# EuclidSeqNano_2020-09-19_20-01-49.net
KiCad netlist of a schematic drawn in EasyEDA
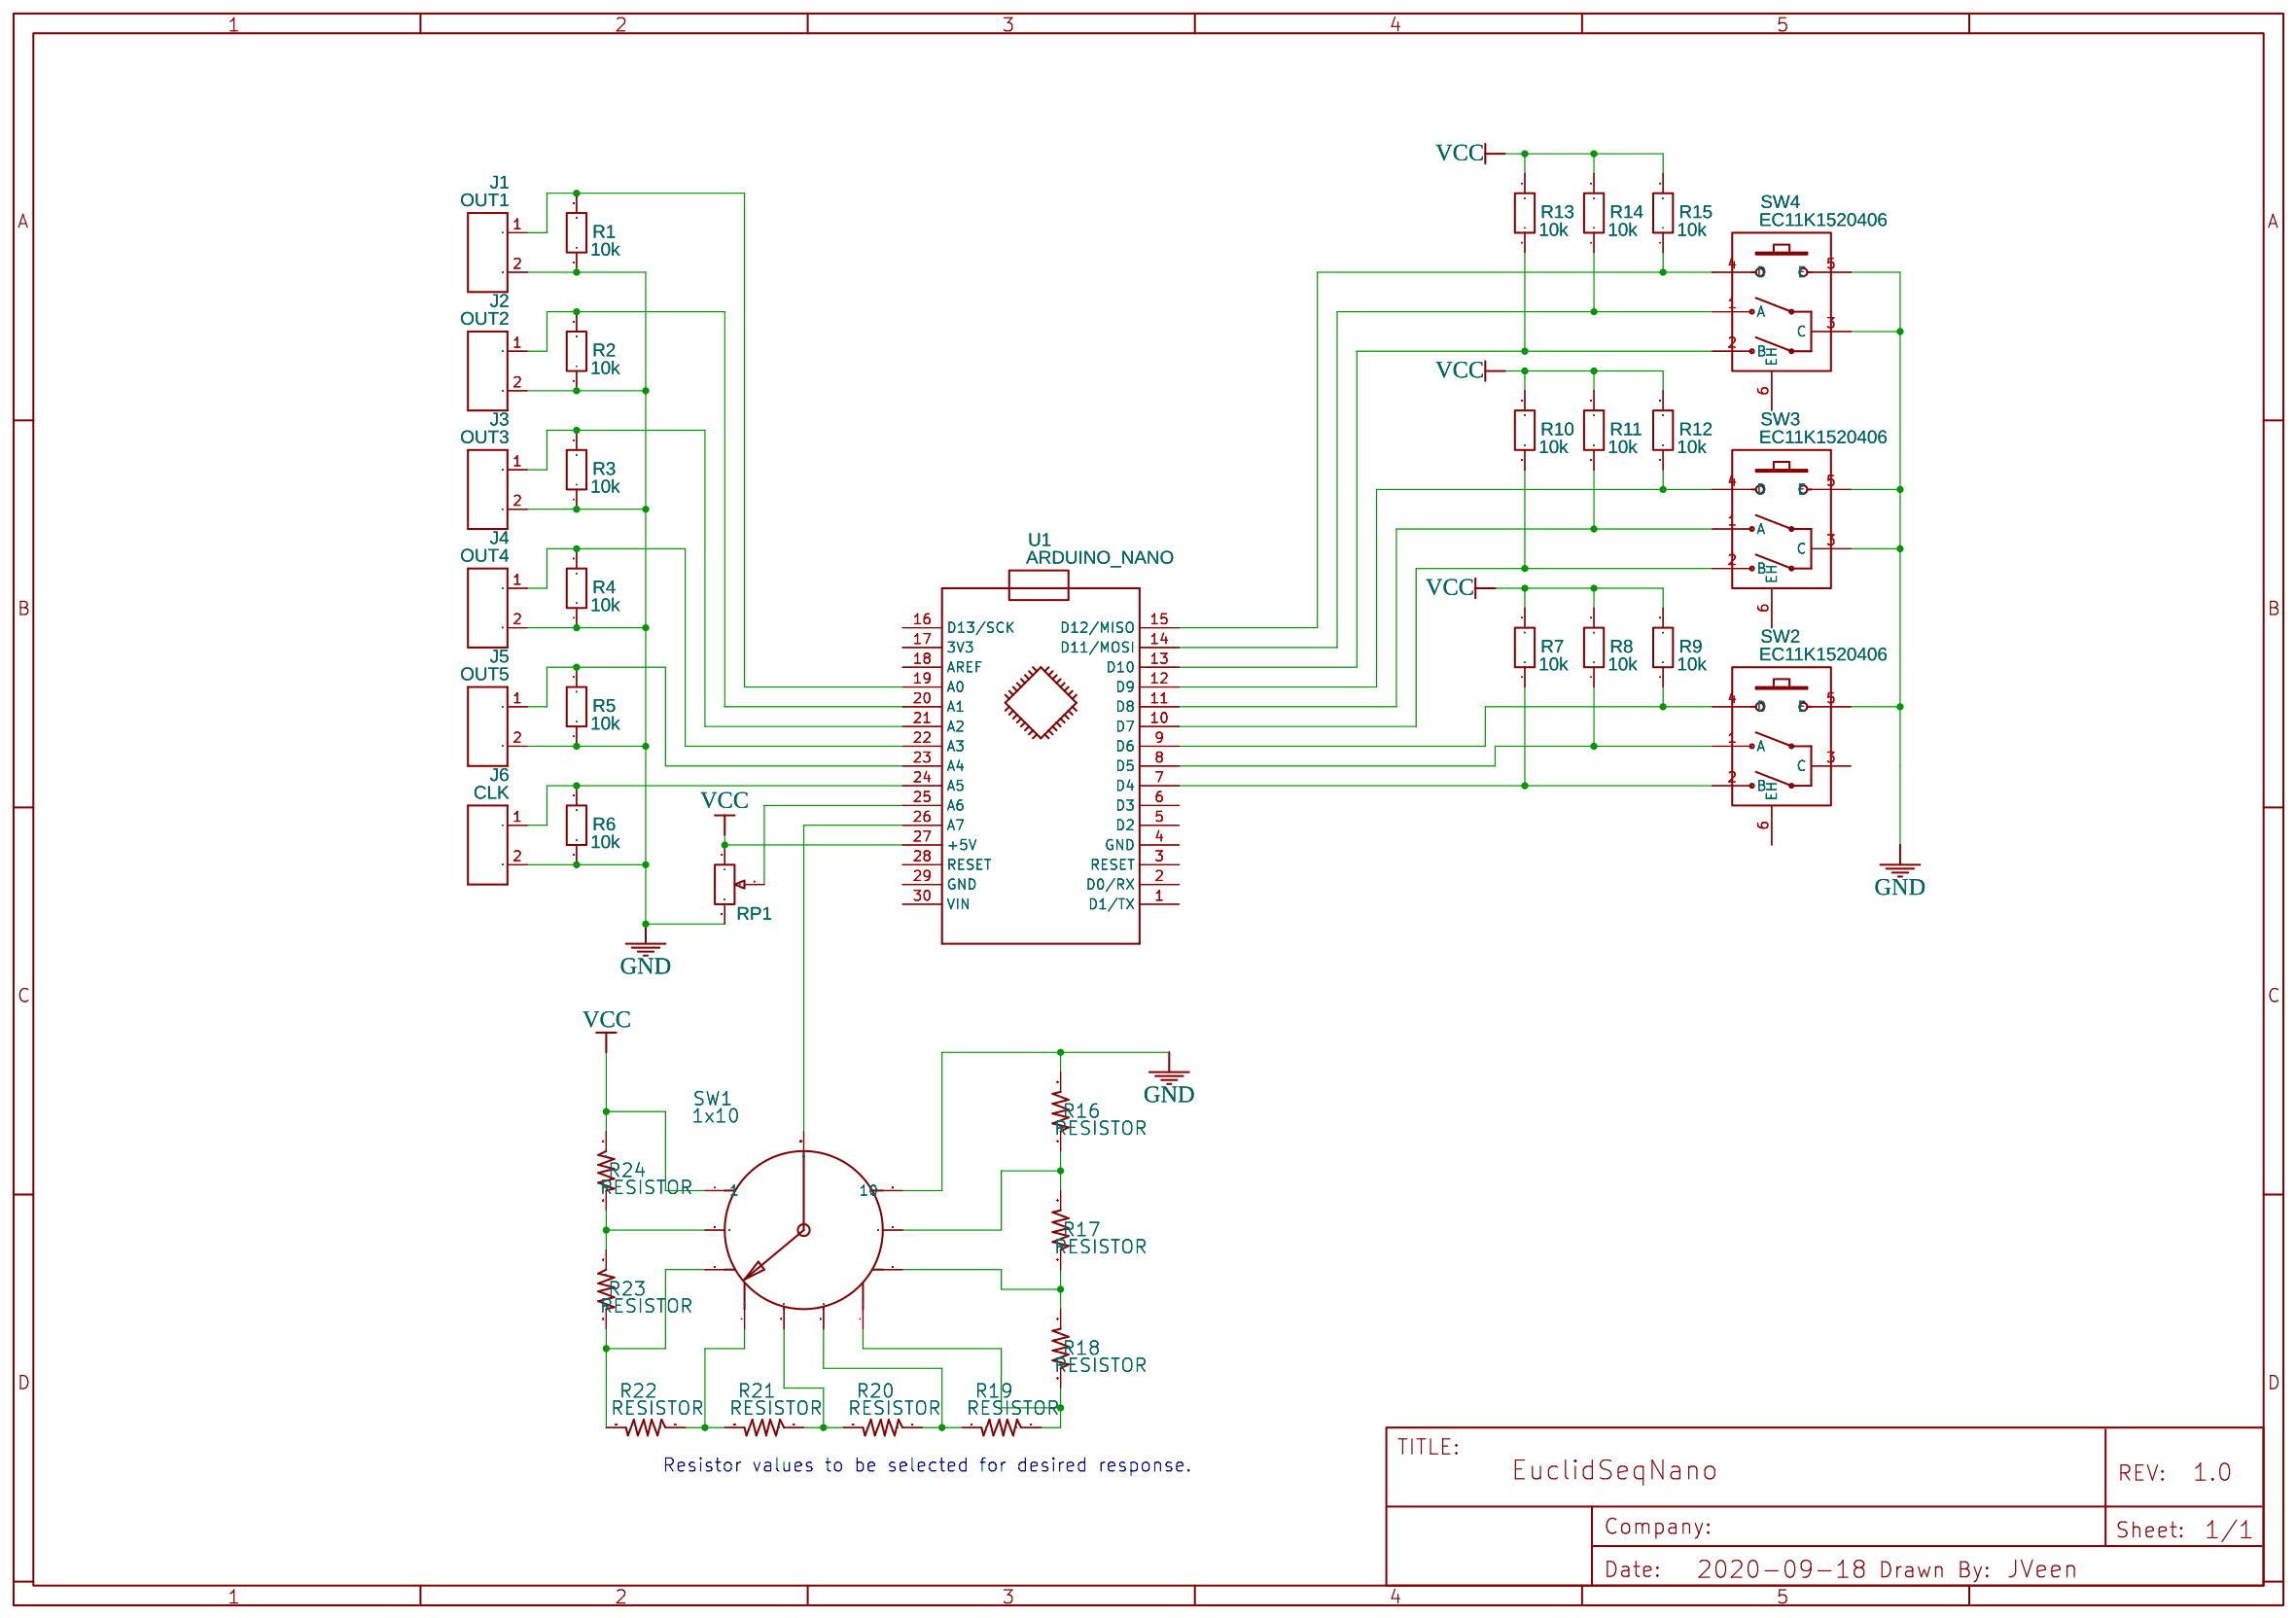
[diagram p0: schematic sheet]

(export (version "E")
  (design (tool "Eeschema 10.0.6"))
  (components
    (comp (ref "J1")
      (value "OUT1")
      (fields (field (name "BOM_Manufacturer Part") "?"))
      (libsource (lib "") (part "Unknown_245_-685"))
    )
    (comp (ref "J2")
      (value "OUT2")
      (fields (field (name "BOM_Manufacturer Part") "?"))
      (libsource (lib "") (part "Unknown_245_-625"))
    )
    (comp (ref "J3")
      (value "OUT3")
      (fields (field (name "BOM_Manufacturer Part") "?"))
      (libsource (lib "") (part "Unknown_245_-565"))
    )
    (comp (ref "J4")
      (value "OUT4")
      (fields (field (name "BOM_Manufacturer Part") "?"))
      (libsource (lib "") (part "Unknown_245_-505"))
    )
    (comp (ref "J5")
      (value "OUT5")
      (fields (field (name "BOM_Manufacturer Part") "?"))
      (libsource (lib "") (part "Unknown_245_-445"))
    )
    (comp (ref "J6")
      (value "CLK")
      (fields (field (name "BOM_Manufacturer Part") "?"))
      (libsource (lib "") (part "Unknown_245_-385"))
    )
    (comp (ref "R1") (value "10k") (libsource (lib "") (part "R_0603_EU")))
    (comp (ref "R2") (value "10k") (libsource (lib "") (part "R_0603_EU")))
    (comp (ref "R3") (value "10k") (libsource (lib "") (part "R_0603_EU")))
    (comp (ref "R4") (value "10k") (libsource (lib "") (part "R_0603_EU")))
    (comp (ref "R5") (value "10k") (libsource (lib "") (part "R_0603_EU")))
    (comp (ref "R6") (value "10k") (libsource (lib "") (part "R_0603_EU")))
    (comp (ref "R7") (value "10k") (libsource (lib "") (part "R_0603_EU")))
    (comp (ref "R8") (value "10k") (libsource (lib "") (part "R_0603_EU")))
    (comp (ref "R9") (value "10k") (libsource (lib "") (part "R_0603_EU")))
    (comp (ref "R10") (value "10k") (libsource (lib "") (part "R_0603_EU")))
    (comp (ref "R11") (value "10k") (libsource (lib "") (part "R_0603_EU")))
    (comp (ref "R12") (value "10k") (libsource (lib "") (part "R_0603_EU")))
    (comp (ref "R13") (value "10k") (libsource (lib "") (part "R_0603_EU")))
    (comp (ref "R14") (value "10k") (libsource (lib "") (part "R_0603_EU")))
    (comp (ref "R15") (value "10k") (libsource (lib "") (part "R_0603_EU")))
    (comp (ref "R16") (value "RESISTOR") (libsource (lib "") (part "Unknown_530_-250")))
    (comp (ref "R17") (value "RESISTOR") (libsource (lib "") (part "Unknown_530_-190")))
    (comp (ref "R18") (value "RESISTOR") (libsource (lib "") (part "Unknown_530_-130")))
    (comp (ref "R19") (value "RESISTOR") (libsource (lib "") (part "Unknown_500_-90")))
    (comp (ref "R20") (value "RESISTOR") (libsource (lib "") (part "Unknown_440_-90")))
    (comp (ref "R21") (value "RESISTOR") (libsource (lib "") (part "Unknown_380_-90")))
    (comp (ref "R22") (value "RESISTOR") (libsource (lib "") (part "Unknown_320_-90")))
    (comp (ref "R23") (value "RESISTOR") (libsource (lib "") (part "Unknown_300_-160")))
    (comp (ref "R24") (value "RESISTOR") (libsource (lib "") (part "Unknown_300_-220")))
    (comp (ref "RP1") (value "R_3386P_EU") (libsource (lib "") (part "R_3386P_EU")))
    (comp (ref "SW1") (value "1x10") (libsource (lib "") (part "Unknown_400_-190")))
    (comp (ref "SW2")
      (value "EC11K1520406")
      (fields (field (name "BOM_Supplier Part") "C470721"))
      (libsource (lib "") (part "EC11K1520406"))
    )
    (comp (ref "SW3")
      (value "EC11K1520406")
      (fields (field (name "BOM_Supplier Part") "C470721"))
      (libsource (lib "") (part "EC11K1520406"))
    )
    (comp (ref "SW4")
      (value "EC11K1520406")
      (fields (field (name "BOM_Supplier Part") "C470721"))
      (libsource (lib "") (part "EC11K1520406"))
    )
    (comp (ref "U1")
      (value "ARDUINO_NANO")
      (fields (field (name "BOM_Manufacturer Part") "?"))
      (libsource (lib "") (part "Unknown_520_-430"))
    )
  )
  (nets
    (net (code "1") (name "GND") (class "Default")
      (node (ref "J1") (pin "2") (pinfunction "2_2") (pintype "unspecified"))
      (node (ref "J2") (pin "2") (pinfunction "2_2") (pintype "unspecified"))
      (node (ref "J3") (pin "2") (pinfunction "2_2") (pintype "unspecified"))
      (node (ref "J4") (pin "2") (pinfunction "2_2") (pintype "unspecified"))
      (node (ref "J5") (pin "2") (pinfunction "2_2") (pintype "unspecified"))
      (node (ref "J6") (pin "2") (pinfunction "2_2") (pintype "unspecified"))
      (node (ref "R1") (pin "1") (pinfunction "1_1") (pintype "unspecified"))
      (node (ref "R16") (pin "P$2") (pinfunction "2_P$2") (pintype "unspecified"))
      (node (ref "R2") (pin "1") (pinfunction "1_1") (pintype "unspecified"))
      (node (ref "R3") (pin "1") (pinfunction "1_1") (pintype "unspecified"))
      (node (ref "R4") (pin "1") (pinfunction "1_1") (pintype "unspecified"))
      (node (ref "R5") (pin "1") (pinfunction "1_1") (pintype "unspecified"))
      (node (ref "R6") (pin "1") (pinfunction "1_1") (pintype "unspecified"))
      (node (ref "RP1") (pin "3") (pinfunction "3_3") (pintype "input"))
      (node (ref "SW1") (pin "10") (pinfunction "10_10") (pintype "unspecified"))
      (node (ref "SW2") (pin "5") (pinfunction "E_5") (pintype "unspecified"))
      (node (ref "SW3") (pin "3") (pinfunction "C_3") (pintype "unspecified"))
      (node (ref "SW3") (pin "5") (pinfunction "E_5") (pintype "unspecified"))
      (node (ref "SW4") (pin "3") (pinfunction "C_3") (pintype "unspecified"))
      (node (ref "SW4") (pin "5") (pinfunction "E_5") (pintype "unspecified"))
    )
    (net (code "2") (name "Net-(R16-1)") (class "Default")
      (node (ref "R16") (pin "P$1") (pinfunction "1_P$1") (pintype "unspecified"))
      (node (ref "R17") (pin "P$2") (pinfunction "2_P$2") (pintype "unspecified"))
      (node (ref "SW1") (pin "9") (pinfunction "9_9") (pintype "unspecified"))
    )
    (net (code "3") (name "Net-(R17-1)") (class "Default")
      (node (ref "R17") (pin "P$1") (pinfunction "1_P$1") (pintype "unspecified"))
      (node (ref "R18") (pin "P$2") (pinfunction "2_P$2") (pintype "unspecified"))
      (node (ref "SW1") (pin "8") (pinfunction "8_8") (pintype "unspecified"))
    )
    (net (code "4") (name "Net-(R18-1)") (class "Default")
      (node (ref "R18") (pin "P$1") (pinfunction "1_P$1") (pintype "unspecified"))
      (node (ref "R19") (pin "P$1") (pinfunction "1_P$1") (pintype "unspecified"))
      (node (ref "SW1") (pin "7") (pinfunction "7_7") (pintype "unspecified"))
    )
    (net (code "5") (name "Net-(R19-2)") (class "Default")
      (node (ref "R19") (pin "P$2") (pinfunction "2_P$2") (pintype "unspecified"))
      (node (ref "R20") (pin "P$1") (pinfunction "1_P$1") (pintype "unspecified"))
      (node (ref "SW1") (pin "6") (pinfunction "6_6") (pintype "unspecified"))
    )
    (net (code "6") (name "Net-(R20-2)") (class "Default")
      (node (ref "R20") (pin "P$2") (pinfunction "2_P$2") (pintype "unspecified"))
      (node (ref "R21") (pin "P$1") (pinfunction "1_P$1") (pintype "unspecified"))
      (node (ref "SW1") (pin "5") (pinfunction "5_5") (pintype "unspecified"))
    )
    (net (code "7") (name "Net-(R21-2)") (class "Default")
      (node (ref "R21") (pin "P$2") (pinfunction "2_P$2") (pintype "unspecified"))
      (node (ref "R22") (pin "P$1") (pinfunction "1_P$1") (pintype "unspecified"))
      (node (ref "SW1") (pin "4") (pinfunction "4_4") (pintype "unspecified"))
    )
    (net (code "8") (name "Net-(R22-2)") (class "Default")
      (node (ref "R22") (pin "P$2") (pinfunction "2_P$2") (pintype "unspecified"))
      (node (ref "R23") (pin "P$2") (pinfunction "2_P$2") (pintype "unspecified"))
      (node (ref "SW1") (pin "3") (pinfunction "3_3") (pintype "unspecified"))
    )
    (net (code "9") (name "Net-(R23-1)") (class "Default")
      (node (ref "R23") (pin "P$1") (pinfunction "1_P$1") (pintype "unspecified"))
      (node (ref "R24") (pin "P$2") (pinfunction "2_P$2") (pintype "unspecified"))
      (node (ref "SW1") (pin "2") (pinfunction "2_2") (pintype "unspecified"))
    )
    (net (code "10") (name "Net-(SW2-A)") (class "Default")
      (node (ref "R8") (pin "1") (pinfunction "1_1") (pintype "unspecified"))
      (node (ref "SW2") (pin "1") (pinfunction "A_1") (pintype "unspecified"))
      (node (ref "U1") (pin "8") (pinfunction "D5_8") (pintype "unspecified"))
    )
    (net (code "11") (name "Net-(SW2-B)") (class "Default")
      (node (ref "R7") (pin "1") (pinfunction "1_1") (pintype "unspecified"))
      (node (ref "SW2") (pin "2") (pinfunction "B_2") (pintype "unspecified"))
      (node (ref "U1") (pin "7") (pinfunction "D4_7") (pintype "unspecified"))
    )
    (net (code "12") (name "Net-(SW2-D)") (class "Default")
      (node (ref "R9") (pin "1") (pinfunction "1_1") (pintype "unspecified"))
      (node (ref "SW2") (pin "4") (pinfunction "D_4") (pintype "unspecified"))
      (node (ref "U1") (pin "9") (pinfunction "D6_9") (pintype "unspecified"))
    )
    (net (code "13") (name "Net-(SW3-A)") (class "Default")
      (node (ref "R11") (pin "1") (pinfunction "1_1") (pintype "unspecified"))
      (node (ref "SW3") (pin "1") (pinfunction "A_1") (pintype "unspecified"))
      (node (ref "U1") (pin "11") (pinfunction "D8_11") (pintype "unspecified"))
    )
    (net (code "14") (name "Net-(SW3-B)") (class "Default")
      (node (ref "R10") (pin "1") (pinfunction "1_1") (pintype "unspecified"))
      (node (ref "SW3") (pin "2") (pinfunction "B_2") (pintype "unspecified"))
      (node (ref "U1") (pin "10") (pinfunction "D7_10") (pintype "unspecified"))
    )
    (net (code "15") (name "Net-(SW3-D)") (class "Default")
      (node (ref "R12") (pin "1") (pinfunction "1_1") (pintype "unspecified"))
      (node (ref "SW3") (pin "4") (pinfunction "D_4") (pintype "unspecified"))
      (node (ref "U1") (pin "12") (pinfunction "D9_12") (pintype "unspecified"))
    )
    (net (code "16") (name "Net-(SW4-A)") (class "Default")
      (node (ref "R14") (pin "1") (pinfunction "1_1") (pintype "unspecified"))
      (node (ref "SW4") (pin "1") (pinfunction "A_1") (pintype "unspecified"))
      (node (ref "U1") (pin "14") (pinfunction "D11/MOSI_14") (pintype "unspecified"))
    )
    (net (code "17") (name "Net-(SW4-B)") (class "Default")
      (node (ref "R13") (pin "1") (pinfunction "1_1") (pintype "unspecified"))
      (node (ref "SW4") (pin "2") (pinfunction "B_2") (pintype "unspecified"))
      (node (ref "U1") (pin "13") (pinfunction "D10_13") (pintype "unspecified"))
    )
    (net (code "18") (name "Net-(SW4-D)") (class "Default")
      (node (ref "R15") (pin "1") (pinfunction "1_1") (pintype "unspecified"))
      (node (ref "SW4") (pin "4") (pinfunction "D_4") (pintype "unspecified"))
      (node (ref "U1") (pin "15") (pinfunction "D12/MISO_15") (pintype "unspecified"))
    )
    (net (code "19") (name "Net-(U1-A0)") (class "Default")
      (node (ref "J1") (pin "1") (pinfunction "1_1") (pintype "unspecified"))
      (node (ref "R1") (pin "2") (pinfunction "2_2") (pintype "unspecified"))
      (node (ref "U1") (pin "19") (pinfunction "A0_19") (pintype "unspecified"))
    )
    (net (code "20") (name "Net-(U1-A1)") (class "Default")
      (node (ref "J2") (pin "1") (pinfunction "1_1") (pintype "unspecified"))
      (node (ref "R2") (pin "2") (pinfunction "2_2") (pintype "unspecified"))
      (node (ref "U1") (pin "20") (pinfunction "A1_20") (pintype "unspecified"))
    )
    (net (code "21") (name "Net-(U1-A2)") (class "Default")
      (node (ref "J3") (pin "1") (pinfunction "1_1") (pintype "unspecified"))
      (node (ref "R3") (pin "2") (pinfunction "2_2") (pintype "unspecified"))
      (node (ref "U1") (pin "21") (pinfunction "A2_21") (pintype "unspecified"))
    )
    (net (code "22") (name "Net-(U1-A3)") (class "Default")
      (node (ref "J4") (pin "1") (pinfunction "1_1") (pintype "unspecified"))
      (node (ref "R4") (pin "2") (pinfunction "2_2") (pintype "unspecified"))
      (node (ref "U1") (pin "22") (pinfunction "A3_22") (pintype "unspecified"))
    )
    (net (code "23") (name "Net-(U1-A4)") (class "Default")
      (node (ref "J5") (pin "1") (pinfunction "1_1") (pintype "unspecified"))
      (node (ref "R5") (pin "2") (pinfunction "2_2") (pintype "unspecified"))
      (node (ref "U1") (pin "23") (pinfunction "A4_23") (pintype "unspecified"))
    )
    (net (code "24") (name "Net-(U1-A5)") (class "Default")
      (node (ref "J6") (pin "1") (pinfunction "1_1") (pintype "unspecified"))
      (node (ref "R6") (pin "2") (pinfunction "2_2") (pintype "unspecified"))
      (node (ref "U1") (pin "24") (pinfunction "A5_24") (pintype "unspecified"))
    )
    (net (code "25") (name "Net-(U1-A6)") (class "Default")
      (node (ref "RP1") (pin "2") (pinfunction "2_2") (pintype "input"))
      (node (ref "U1") (pin "25") (pinfunction "A6_25") (pintype "unspecified"))
    )
    (net (code "26") (name "Net-(U1-A7)") (class "Default")
      (node (ref "SW1") (pin "COMMON") (pinfunction "COMMON_COMMON") (pintype "unspecified"))
      (node (ref "U1") (pin "26") (pinfunction "A7_26") (pintype "unspecified"))
    )
    (net (code "27") (name "VCC") (class "Default")
      (node (ref "R10") (pin "2") (pinfunction "2_2") (pintype "unspecified"))
      (node (ref "R11") (pin "2") (pinfunction "2_2") (pintype "unspecified"))
      (node (ref "R12") (pin "2") (pinfunction "2_2") (pintype "unspecified"))
      (node (ref "R13") (pin "2") (pinfunction "2_2") (pintype "unspecified"))
      (node (ref "R14") (pin "2") (pinfunction "2_2") (pintype "unspecified"))
      (node (ref "R15") (pin "2") (pinfunction "2_2") (pintype "unspecified"))
      (node (ref "R24") (pin "P$1") (pinfunction "1_P$1") (pintype "unspecified"))
      (node (ref "R7") (pin "2") (pinfunction "2_2") (pintype "unspecified"))
      (node (ref "R8") (pin "2") (pinfunction "2_2") (pintype "unspecified"))
      (node (ref "R9") (pin "2") (pinfunction "2_2") (pintype "unspecified"))
      (node (ref "RP1") (pin "1") (pinfunction "1_1") (pintype "input"))
      (node (ref "SW1") (pin "1") (pinfunction "1_1") (pintype "unspecified"))
      (node (ref "U1") (pin "27") (pinfunction "+5V_27") (pintype "unspecified"))
    )
    (net (code "28") (name "unconnected-(SW2-C-Pad3)") (class "Default")
      (node (ref "SW2") (pin "3") (pinfunction "C_3") (pintype "unspecified"))
    )
    (net (code "29") (name "unconnected-(SW2-EH-Pad6)") (class "Default")
      (node (ref "SW2") (pin "6") (pinfunction "EH_6") (pintype "unspecified"))
    )
    (net (code "30") (name "unconnected-(SW3-EH-Pad6)") (class "Default")
      (node (ref "SW3") (pin "6") (pinfunction "EH_6") (pintype "unspecified"))
    )
    (net (code "31") (name "unconnected-(SW4-EH-Pad6)") (class "Default")
      (node (ref "SW4") (pin "6") (pinfunction "EH_6") (pintype "unspecified"))
    )
    (net (code "32") (name "unconnected-(U1-3V3-Pad17)") (class "Default")
      (node (ref "U1") (pin "17") (pinfunction "3V3_17") (pintype "unspecified"))
    )
    (net (code "33") (name "unconnected-(U1-AREF-Pad18)") (class "Default")
      (node (ref "U1") (pin "18") (pinfunction "AREF_18") (pintype "unspecified"))
    )
    (net (code "34") (name "unconnected-(U1-D0{slash}RX-Pad2)") (class "Default")
      (node (ref "U1") (pin "2") (pinfunction "D0/RX_2") (pintype "unspecified"))
    )
    (net (code "35") (name "unconnected-(U1-D1{slash}TX-Pad1)") (class "Default")
      (node (ref "U1") (pin "1") (pinfunction "D1/TX_1") (pintype "unspecified"))
    )
    (net (code "36") (name "unconnected-(U1-D2-Pad5)") (class "Default")
      (node (ref "U1") (pin "5") (pinfunction "D2_5") (pintype "unspecified"))
    )
    (net (code "37") (name "unconnected-(U1-D3-Pad6)") (class "Default")
      (node (ref "U1") (pin "6") (pinfunction "D3_6") (pintype "unspecified"))
    )
    (net (code "38") (name "unconnected-(U1-D13{slash}SCK-Pad16)") (class "Default")
      (node (ref "U1") (pin "16") (pinfunction "D13/SCK_16") (pintype "unspecified"))
    )
    (net (code "39") (name "unconnected-(U1-GND-Pad4)") (class "Default")
      (node (ref "U1") (pin "4") (pinfunction "GND_4") (pintype "unspecified"))
    )
    (net (code "40") (name "unconnected-(U1-GND-Pad29)") (class "Default")
      (node (ref "U1") (pin "29") (pinfunction "GND_29") (pintype "unspecified"))
    )
    (net (code "41") (name "unconnected-(U1-RESET-Pad3)") (class "Default")
      (node (ref "U1") (pin "3") (pinfunction "RESET_3") (pintype "unspecified"))
    )
    (net (code "42") (name "unconnected-(U1-RESET-Pad28)") (class "Default")
      (node (ref "U1") (pin "28") (pinfunction "RESET_28") (pintype "unspecified"))
    )
    (net (code "43") (name "unconnected-(U1-VIN-Pad30)") (class "Default")
      (node (ref "U1") (pin "30") (pinfunction "VIN_30") (pintype "unspecified"))
    )
  )
)
